# Digital_CPLD.net
KiCad netlist of a schematic drawn in Altium Designer
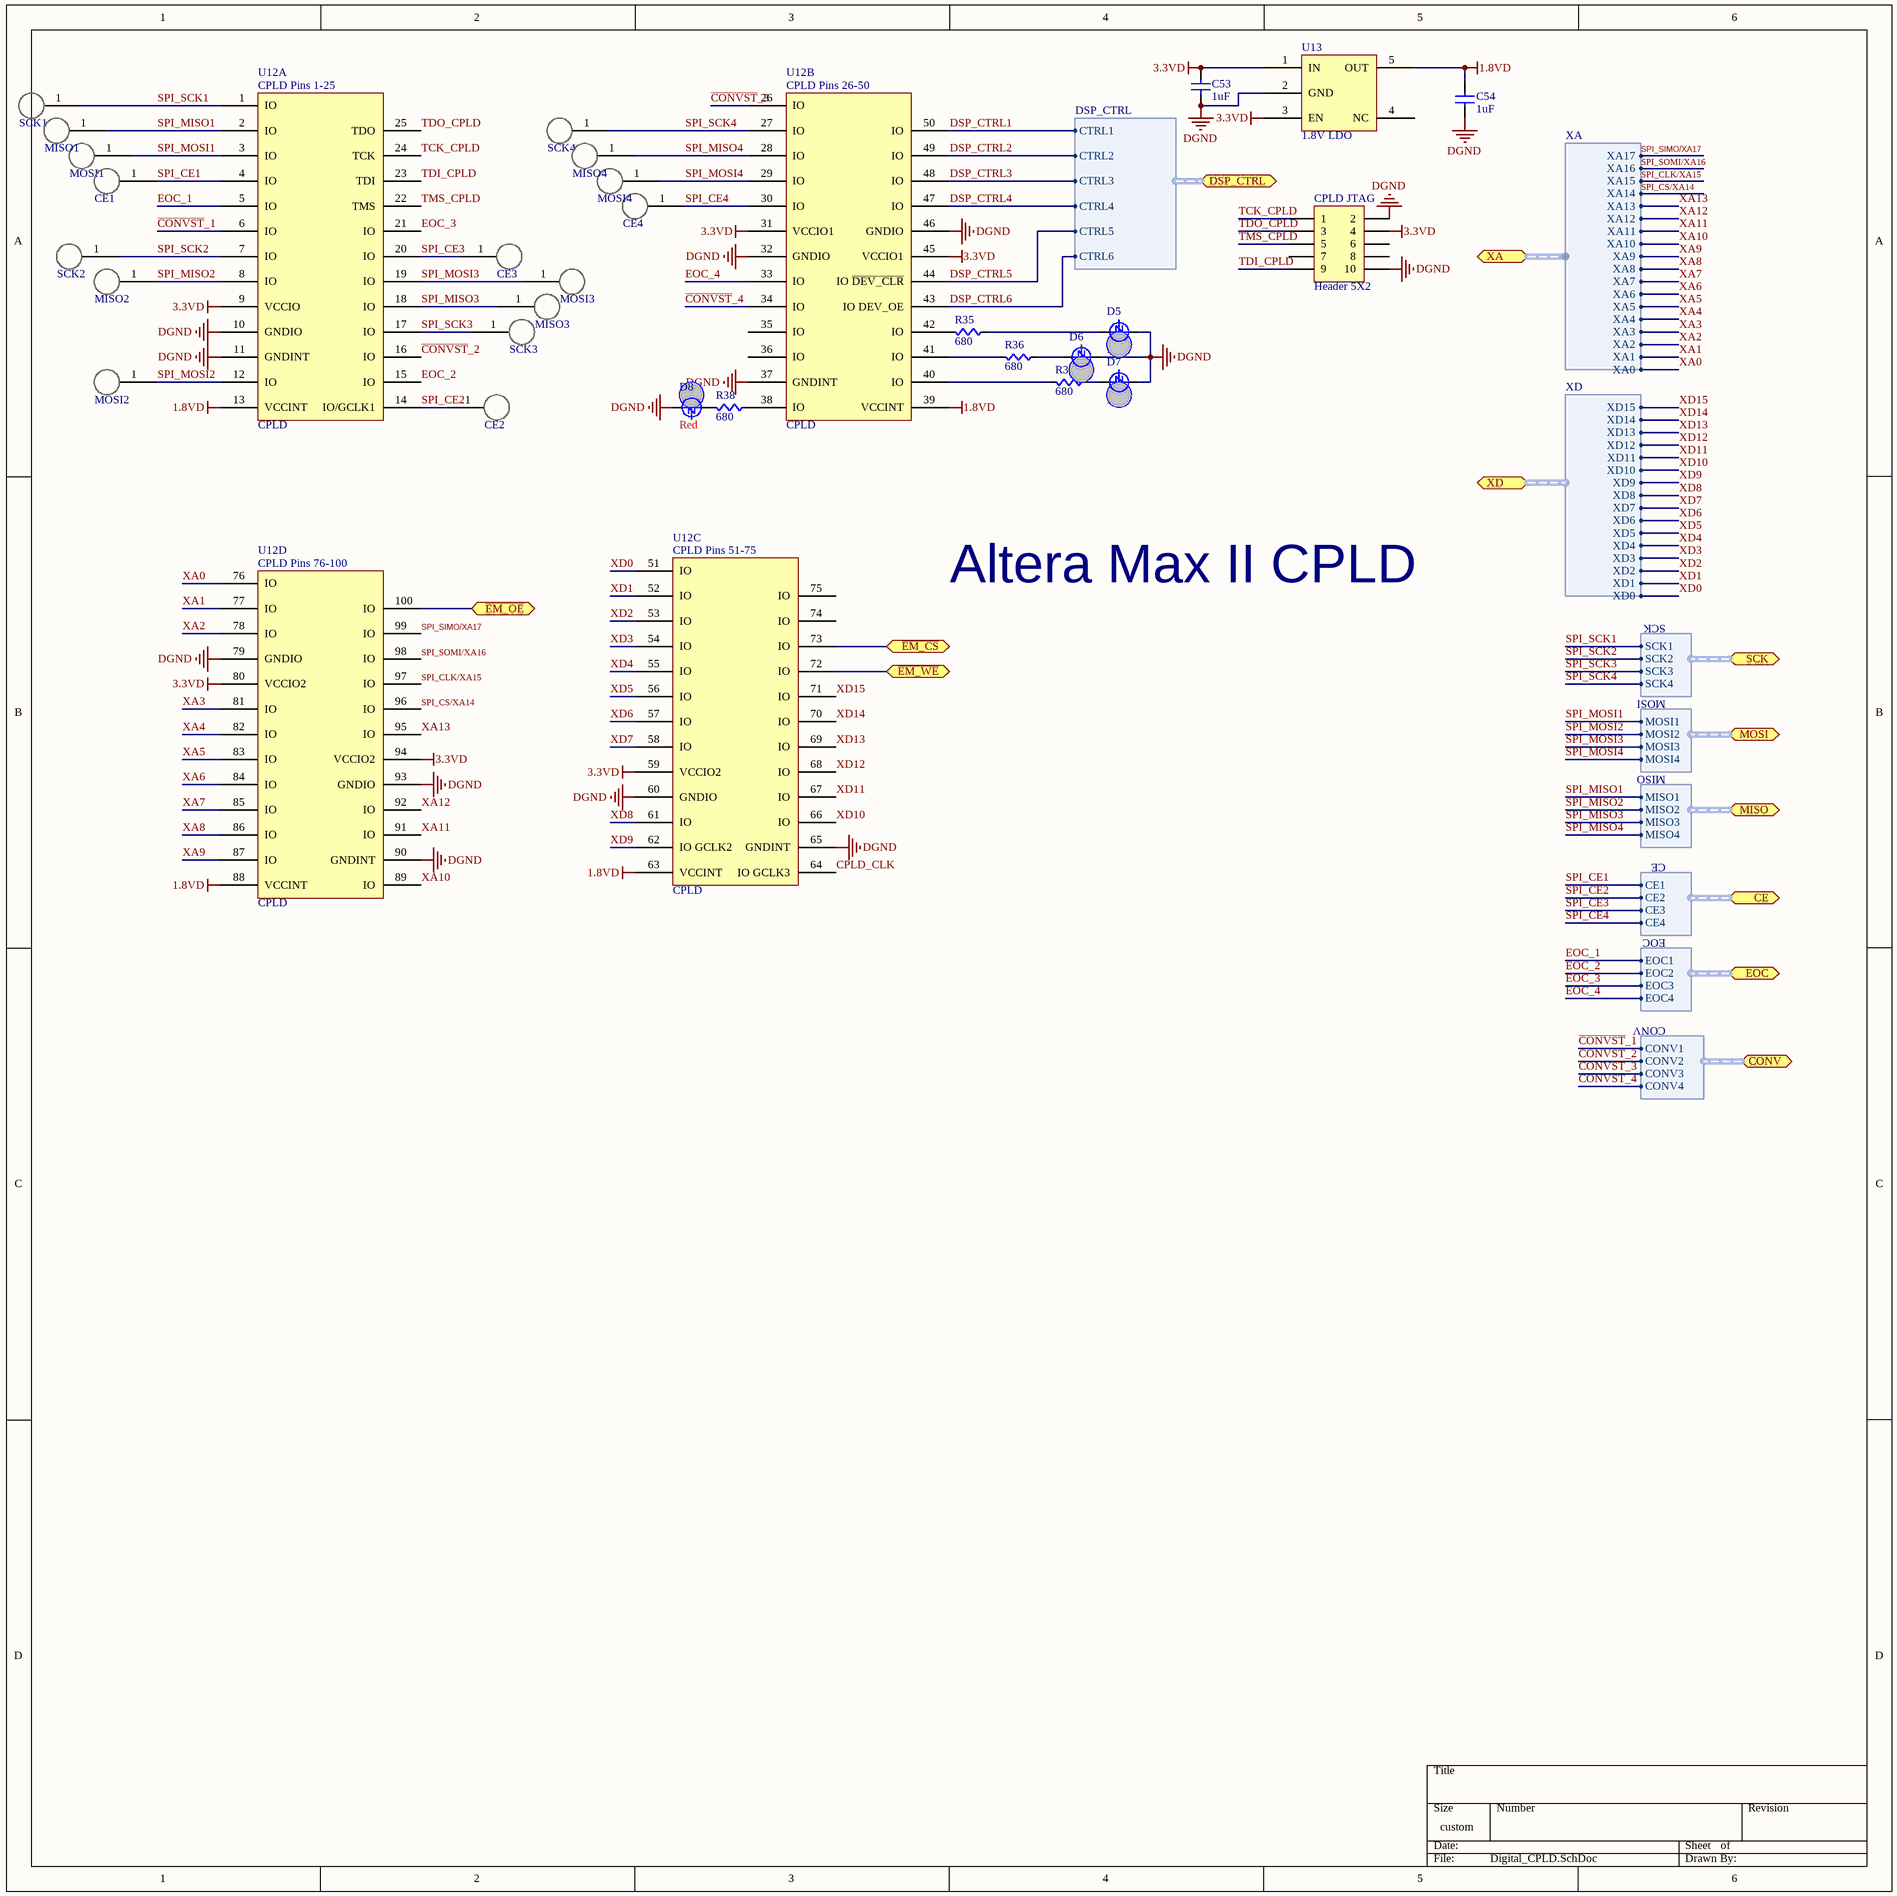
[diagram p0: Digital_CPLD.SchDoc]

(export (version "E")
  (design (tool "Eeschema 10.0.6"))
  (components
    (comp (ref "C53")
      (value "1uF")
      (footprint "CAPC0603")
      (fields (field (name "Comment") "Cap"))
      (libsource (lib "SubjuGator8") (part "Cap"))
    )
    (comp (ref "C54")
      (value "1uF")
      (footprint "CAPC0603")
      (fields (field (name "Comment") "Cap"))
      (libsource (lib "SubjuGator8") (part "Cap"))
    )
    (comp (ref "CE1")
      (value "Test_Point")
      (footprint "TP")
      (description "TEST POINT PC COMPACT .063\"D")
      (libsource (lib "Hydrophone") (part "Test_Point"))
    )
    (comp (ref "CE2")
      (value "Test_Point")
      (footprint "TP")
      (description "TEST POINT PC COMPACT .063\"D")
      (libsource (lib "Hydrophone") (part "Test_Point"))
    )
    (comp (ref "CE3")
      (value "Test_Point")
      (footprint "TP")
      (description "TEST POINT PC COMPACT .063\"D")
      (libsource (lib "Hydrophone") (part "Test_Point"))
    )
    (comp (ref "CE4")
      (value "Test_Point")
      (footprint "TP")
      (description "TEST POINT PC COMPACT .063\"D")
      (libsource (lib "Hydrophone") (part "Test_Point"))
    )
    (comp (ref "CPLD JTAG")
      (value "Header 5X2")
      (footprint "HDR2X5")
      (description "Header, 5-Pin, Dual row")
      (fields (field (name "PUBLISHER") "Altium Limited"))
      (libsource (lib "Miscellaneous Connectors") (part "Header 5X2"))
    )
    (comp (ref "D5")
      (value "LED")
      (footprint "LED0603")
      (fields (field (name "COLOR") "Red"))
      (libsource (lib "SubjuGator8") (part "LED"))
    )
    (comp (ref "D6")
      (value "LED")
      (footprint "LED0603")
      (fields (field (name "COLOR") "Red"))
      (libsource (lib "SubjuGator8") (part "LED"))
    )
    (comp (ref "D7")
      (value "LED")
      (footprint "LED0603")
      (fields (field (name "COLOR") "Red"))
      (libsource (lib "SubjuGator8") (part "LED"))
    )
    (comp (ref "D8")
      (value "LED")
      (footprint "LED0603")
      (fields (field (name "COLOR") "Red"))
      (libsource (lib "") (part "LED_1"))
    )
    (comp (ref "MISO1")
      (value "Test_Point")
      (footprint "TP")
      (description "TEST POINT PC COMPACT .063\"D")
      (libsource (lib "Hydrophone") (part "Test_Point"))
    )
    (comp (ref "MISO2")
      (value "Test_Point")
      (footprint "TP")
      (description "TEST POINT PC COMPACT .063\"D")
      (libsource (lib "Hydrophone") (part "Test_Point"))
    )
    (comp (ref "MISO3")
      (value "Test_Point")
      (footprint "TP")
      (description "TEST POINT PC COMPACT .063\"D")
      (libsource (lib "Hydrophone") (part "Test_Point"))
    )
    (comp (ref "MISO4")
      (value "Test_Point")
      (footprint "TP")
      (description "TEST POINT PC COMPACT .063\"D")
      (libsource (lib "Hydrophone") (part "Test_Point"))
    )
    (comp (ref "MOSI1")
      (value "Test_Point")
      (footprint "TP")
      (description "TEST POINT PC COMPACT .063\"D")
      (libsource (lib "Hydrophone") (part "Test_Point"))
    )
    (comp (ref "MOSI2")
      (value "Test_Point")
      (footprint "TP")
      (description "TEST POINT PC COMPACT .063\"D")
      (libsource (lib "Hydrophone") (part "Test_Point"))
    )
    (comp (ref "MOSI3")
      (value "Test_Point")
      (footprint "TP")
      (description "TEST POINT PC COMPACT .063\"D")
      (libsource (lib "Hydrophone") (part "Test_Point"))
    )
    (comp (ref "MOSI4")
      (value "Test_Point")
      (footprint "TP")
      (description "TEST POINT PC COMPACT .063\"D")
      (libsource (lib "Hydrophone") (part "Test_Point"))
    )
    (comp (ref "R35")
      (value "680")
      (footprint "RES0603")
      (fields (field (name "Comment") "Res"))
      (libsource (lib "SubjuGator8") (part "Res"))
    )
    (comp (ref "R36")
      (value "680")
      (footprint "RES0603")
      (fields (field (name "Comment") "Res"))
      (libsource (lib "SubjuGator8") (part "Res"))
    )
    (comp (ref "R37")
      (value "680")
      (footprint "RES0603")
      (fields (field (name "Comment") "Res"))
      (libsource (lib "SubjuGator8") (part "Res"))
    )
    (comp (ref "R38")
      (value "680")
      (footprint "RES0603")
      (fields (field (name "Comment") "Res"))
      (libsource (lib "SubjuGator8") (part "Res"))
    )
    (comp (ref "SCK1")
      (value "Test_Point")
      (footprint "TP")
      (description "TEST POINT PC COMPACT .063\"D")
      (libsource (lib "Hydrophone") (part "Test_Point"))
    )
    (comp (ref "SCK2")
      (value "Test_Point")
      (footprint "TP")
      (description "TEST POINT PC COMPACT .063\"D")
      (libsource (lib "Hydrophone") (part "Test_Point"))
    )
    (comp (ref "SCK3")
      (value "Test_Point")
      (footprint "TP")
      (description "TEST POINT PC COMPACT .063\"D")
      (libsource (lib "Hydrophone") (part "Test_Point"))
    )
    (comp (ref "SCK4")
      (value "Test_Point")
      (footprint "TP")
      (description "TEST POINT PC COMPACT .063\"D")
      (libsource (lib "Hydrophone") (part "Test_Point"))
    )
    (comp (ref "U12")
      (value "CPLD")
      (footprint "TQFP-100")
      (description "IC CPLD 192MC 4.7NS 100TQFP")
      (libsource (lib "SubjuGator8") (part "EPM240GT100I5N"))
    )
    (comp (ref "U13")
      (value "1.8V LDO")
      (footprint "SOT23-5n")
      (description "IC REG LDO 1.8V 0.25A SOT23-5")
      (libsource (lib "SubjuGator8") (part "LP5907"))
    )
  )
  (nets
    (net (code "10") (name "/CPLD_CLK") (class "Default")
      (node (ref "U12") (pin "64") (pinfunction "IO_GCLK3_64") (pintype "passive"))
    )
    (net (code "11") (name "/DSP_CTRL1") (class "Default")
      (node (ref "U12") (pin "50") (pinfunction "IO_50") (pintype "passive"))
    )
    (net (code "12") (name "/DSP_CTRL2") (class "Default")
      (node (ref "U12") (pin "49") (pinfunction "IO_49") (pintype "passive"))
    )
    (net (code "13") (name "/DSP_CTRL3") (class "Default")
      (node (ref "U12") (pin "48") (pinfunction "IO_48") (pintype "passive"))
    )
    (net (code "14") (name "/DSP_CTRL4") (class "Default")
      (node (ref "U12") (pin "47") (pinfunction "IO_47") (pintype "passive"))
    )
    (net (code "15") (name "/DSP_CTRL5") (class "Default")
      (node (ref "U12") (pin "44") (pinfunction "IO_~{DEV_CLR}_44") (pintype "passive"))
    )
    (net (code "16") (name "/DSP_CTRL6") (class "Default")
      (node (ref "U12") (pin "43") (pinfunction "IO_DEV_OE_43") (pintype "passive"))
    )
    (net (code "17") (name "/EOC_1") (class "Default")
      (node (ref "U12") (pin "5") (pinfunction "IO_5") (pintype "passive"))
    )
    (net (code "18") (name "/EOC_2") (class "Default")
      (node (ref "U12") (pin "15") (pinfunction "IO_15") (pintype "passive"))
    )
    (net (code "19") (name "/EOC_3") (class "Default")
      (node (ref "U12") (pin "21") (pinfunction "IO_21") (pintype "passive"))
    )
    (net (code "20") (name "/EOC_4") (class "Default")
      (node (ref "U12") (pin "33") (pinfunction "IO_33") (pintype "passive"))
    )
    (net (code "21") (name "/SPI_CE1") (class "Default")
      (node (ref "CE1") (pin "1") (pintype "passive"))
      (node (ref "U12") (pin "4") (pinfunction "IO_4") (pintype "passive"))
    )
    (net (code "22") (name "/SPI_CE2") (class "Default")
      (node (ref "CE2") (pin "1") (pintype "passive"))
      (node (ref "U12") (pin "14") (pinfunction "IO/GCLK1_14") (pintype "passive"))
    )
    (net (code "23") (name "/SPI_CE3") (class "Default")
      (node (ref "CE3") (pin "1") (pintype "passive"))
      (node (ref "U12") (pin "20") (pinfunction "IO_20") (pintype "passive"))
    )
    (net (code "24") (name "/SPI_CE4") (class "Default")
      (node (ref "CE4") (pin "1") (pintype "passive"))
      (node (ref "U12") (pin "30") (pinfunction "IO_30") (pintype "passive"))
    )
    (net (code "25") (name "/SPI_CLK{slash}XA15") (class "Default")
      (node (ref "U12") (pin "97") (pinfunction "IO_97") (pintype "passive"))
    )
    (net (code "26") (name "/SPI_CS{slash}XA14") (class "Default")
      (node (ref "U12") (pin "96") (pinfunction "IO_96") (pintype "passive"))
    )
    (net (code "27") (name "/SPI_MISO1") (class "Default")
      (node (ref "MISO1") (pin "1") (pintype "passive"))
      (node (ref "U12") (pin "2") (pinfunction "IO_2") (pintype "passive"))
    )
    (net (code "28") (name "/SPI_MISO2") (class "Default")
      (node (ref "MISO2") (pin "1") (pintype "passive"))
      (node (ref "U12") (pin "8") (pinfunction "IO_8") (pintype "passive"))
    )
    (net (code "29") (name "/SPI_MISO3") (class "Default")
      (node (ref "MISO3") (pin "1") (pintype "passive"))
      (node (ref "U12") (pin "18") (pinfunction "IO_18") (pintype "passive"))
    )
    (net (code "30") (name "/SPI_MISO4") (class "Default")
      (node (ref "MISO4") (pin "1") (pintype "passive"))
      (node (ref "U12") (pin "28") (pinfunction "IO_28") (pintype "passive"))
    )
    (net (code "31") (name "/SPI_MOSI1") (class "Default")
      (node (ref "MOSI1") (pin "1") (pintype "passive"))
      (node (ref "U12") (pin "3") (pinfunction "IO_3") (pintype "passive"))
    )
    (net (code "32") (name "/SPI_MOSI2") (class "Default")
      (node (ref "MOSI2") (pin "1") (pintype "passive"))
      (node (ref "U12") (pin "12") (pinfunction "IO_12") (pintype "passive"))
    )
    (net (code "33") (name "/SPI_MOSI3") (class "Default")
      (node (ref "MOSI3") (pin "1") (pintype "passive"))
      (node (ref "U12") (pin "19") (pinfunction "IO_19") (pintype "passive"))
    )
    (net (code "34") (name "/SPI_MOSI4") (class "Default")
      (node (ref "MOSI4") (pin "1") (pintype "passive"))
      (node (ref "U12") (pin "29") (pinfunction "IO_29") (pintype "passive"))
    )
    (net (code "35") (name "/SPI_SCK1") (class "Default")
      (node (ref "SCK1") (pin "1") (pintype "passive"))
      (node (ref "U12") (pin "1") (pinfunction "IO_1") (pintype "passive"))
    )
    (net (code "36") (name "/SPI_SCK2") (class "Default")
      (node (ref "SCK2") (pin "1") (pintype "passive"))
      (node (ref "U12") (pin "7") (pinfunction "IO_7") (pintype "passive"))
    )
    (net (code "37") (name "/SPI_SCK3") (class "Default")
      (node (ref "SCK3") (pin "1") (pintype "passive"))
      (node (ref "U12") (pin "17") (pinfunction "IO_17") (pintype "passive"))
    )
    (net (code "38") (name "/SPI_SCK4") (class "Default")
      (node (ref "SCK4") (pin "1") (pintype "passive"))
      (node (ref "U12") (pin "27") (pinfunction "IO_27") (pintype "passive"))
    )
    (net (code "39") (name "/SPI_SIMO{slash}XA17") (class "Default")
      (node (ref "U12") (pin "99") (pinfunction "IO_99") (pintype "passive"))
    )
    (net (code "40") (name "/SPI_SOMI{slash}XA16") (class "Default")
      (node (ref "U12") (pin "98") (pinfunction "IO_98") (pintype "passive"))
    )
    (net (code "41") (name "/TCK_CPLD") (class "Default")
      (node (ref "CPLD JTAG") (pin "1") (pinfunction "1_1") (pintype "passive"))
      (node (ref "U12") (pin "24") (pinfunction "TCK_24") (pintype "passive"))
    )
    (net (code "42") (name "/TDI_CPLD") (class "Default")
      (node (ref "CPLD JTAG") (pin "9") (pinfunction "9_9") (pintype "passive"))
      (node (ref "U12") (pin "23") (pinfunction "TDI_23") (pintype "passive"))
    )
    (net (code "43") (name "/TDO_CPLD") (class "Default")
      (node (ref "CPLD JTAG") (pin "3") (pinfunction "3_3") (pintype "passive"))
      (node (ref "U12") (pin "25") (pinfunction "TDO_25") (pintype "passive"))
    )
    (net (code "44") (name "/TMS_CPLD") (class "Default")
      (node (ref "CPLD JTAG") (pin "5") (pinfunction "5_5") (pintype "passive"))
      (node (ref "U12") (pin "22") (pinfunction "TMS_22") (pintype "passive"))
    )
    (net (code "45") (name "/XA0") (class "Default")
      (node (ref "U12") (pin "76") (pinfunction "IO_76") (pintype "passive"))
    )
    (net (code "46") (name "/XA1") (class "Default")
      (node (ref "U12") (pin "77") (pinfunction "IO_77") (pintype "passive"))
    )
    (net (code "47") (name "/XA2") (class "Default")
      (node (ref "U12") (pin "78") (pinfunction "IO_78") (pintype "passive"))
    )
    (net (code "48") (name "/XA3") (class "Default")
      (node (ref "U12") (pin "81") (pinfunction "IO_81") (pintype "passive"))
    )
    (net (code "49") (name "/XA4") (class "Default")
      (node (ref "U12") (pin "82") (pinfunction "IO_82") (pintype "passive"))
    )
    (net (code "50") (name "/XA5") (class "Default")
      (node (ref "U12") (pin "83") (pinfunction "IO_83") (pintype "passive"))
    )
    (net (code "51") (name "/XA6") (class "Default")
      (node (ref "U12") (pin "84") (pinfunction "IO_84") (pintype "passive"))
    )
    (net (code "52") (name "/XA7") (class "Default")
      (node (ref "U12") (pin "85") (pinfunction "IO_85") (pintype "passive"))
    )
    (net (code "53") (name "/XA8") (class "Default")
      (node (ref "U12") (pin "86") (pinfunction "IO_86") (pintype "passive"))
    )
    (net (code "54") (name "/XA9") (class "Default")
      (node (ref "U12") (pin "87") (pinfunction "IO_87") (pintype "passive"))
    )
    (net (code "55") (name "/XA10") (class "Default")
      (node (ref "U12") (pin "89") (pinfunction "IO_89") (pintype "passive"))
    )
    (net (code "56") (name "/XA11") (class "Default")
      (node (ref "U12") (pin "91") (pinfunction "IO_91") (pintype "passive"))
    )
    (net (code "57") (name "/XA12") (class "Default")
      (node (ref "U12") (pin "92") (pinfunction "IO_92") (pintype "passive"))
    )
    (net (code "58") (name "/XA13") (class "Default")
      (node (ref "U12") (pin "95") (pinfunction "IO_95") (pintype "passive"))
    )
    (net (code "59") (name "/XD0") (class "Default")
      (node (ref "U12") (pin "51") (pinfunction "IO_51") (pintype "passive"))
    )
    (net (code "60") (name "/XD1") (class "Default")
      (node (ref "U12") (pin "52") (pinfunction "IO_52") (pintype "passive"))
    )
    (net (code "61") (name "/XD2") (class "Default")
      (node (ref "U12") (pin "53") (pinfunction "IO_53") (pintype "passive"))
    )
    (net (code "62") (name "/XD3") (class "Default")
      (node (ref "U12") (pin "54") (pinfunction "IO_54") (pintype "passive"))
    )
    (net (code "63") (name "/XD4") (class "Default")
      (node (ref "U12") (pin "55") (pinfunction "IO_55") (pintype "passive"))
    )
    (net (code "64") (name "/XD5") (class "Default")
      (node (ref "U12") (pin "56") (pinfunction "IO_56") (pintype "passive"))
    )
    (net (code "65") (name "/XD6") (class "Default")
      (node (ref "U12") (pin "57") (pinfunction "IO_57") (pintype "passive"))
    )
    (net (code "66") (name "/XD7") (class "Default")
      (node (ref "U12") (pin "58") (pinfunction "IO_58") (pintype "passive"))
    )
    (net (code "67") (name "/XD8") (class "Default")
      (node (ref "U12") (pin "61") (pinfunction "IO_61") (pintype "passive"))
    )
    (net (code "68") (name "/XD9") (class "Default")
      (node (ref "U12") (pin "62") (pinfunction "IO_GCLK2_62") (pintype "passive"))
    )
    (net (code "69") (name "/XD10") (class "Default")
      (node (ref "U12") (pin "66") (pinfunction "IO_66") (pintype "passive"))
    )
    (net (code "70") (name "/XD11") (class "Default")
      (node (ref "U12") (pin "67") (pinfunction "IO_67") (pintype "passive"))
    )
    (net (code "71") (name "/XD12") (class "Default")
      (node (ref "U12") (pin "68") (pinfunction "IO_68") (pintype "passive"))
    )
    (net (code "72") (name "/XD13") (class "Default")
      (node (ref "U12") (pin "69") (pinfunction "IO_69") (pintype "passive"))
    )
    (net (code "73") (name "/XD14") (class "Default")
      (node (ref "U12") (pin "70") (pinfunction "IO_70") (pintype "passive"))
    )
    (net (code "74") (name "/XD15") (class "Default")
      (node (ref "U12") (pin "71") (pinfunction "IO_71") (pintype "passive"))
    )
    (net (code "84") (name "/~{CONVST}_1") (class "Default")
      (node (ref "U12") (pin "6") (pinfunction "IO_6") (pintype "passive"))
    )
    (net (code "85") (name "/~{CONVST}_2") (class "Default")
      (node (ref "U12") (pin "16") (pinfunction "IO_16") (pintype "passive"))
    )
    (net (code "86") (name "/~{CONVST}_3") (class "Default")
      (node (ref "U12") (pin "26") (pinfunction "IO_26") (pintype "passive"))
    )
    (net (code "87") (name "/~{CONVST}_4") (class "Default")
      (node (ref "U12") (pin "34") (pinfunction "IO_34") (pintype "passive"))
    )
    (net (code "88") (name "/~{EM_CS}") (class "Default")
      (node (ref "U12") (pin "73") (pinfunction "IO_73") (pintype "passive"))
    )
    (net (code "89") (name "/~{EM_OE}") (class "Default")
      (node (ref "U12") (pin "100") (pinfunction "IO_100") (pintype "passive"))
    )
    (net (code "90") (name "/~{EM_WE}") (class "Default")
      (node (ref "U12") (pin "72") (pinfunction "IO_72") (pintype "passive"))
    )
    (net (code "91") (name "1.8VD") (class "Default")
      (node (ref "C54") (pin "1") (pinfunction "A_1") (pintype "passive"))
      (node (ref "U12") (pin "13") (pinfunction "VCCINT_13") (pintype "passive"))
      (node (ref "U12") (pin "39") (pinfunction "VCCINT_39") (pintype "passive"))
      (node (ref "U12") (pin "63") (pinfunction "VCCINT_63") (pintype "passive"))
      (node (ref "U12") (pin "88") (pinfunction "VCCINT_88") (pintype "passive"))
      (node (ref "U13") (pin "5") (pinfunction "OUT_5") (pintype "passive"))
    )
    (net (code "92") (name "3.3VD") (class "Default")
      (node (ref "C53") (pin "1") (pinfunction "A_1") (pintype "passive"))
      (node (ref "CPLD JTAG") (pin "4") (pinfunction "4_4") (pintype "passive"))
      (node (ref "U12") (pin "31") (pinfunction "VCCIO1_31") (pintype "passive"))
      (node (ref "U12") (pin "45") (pinfunction "VCCIO1_45") (pintype "passive"))
      (node (ref "U12") (pin "59") (pinfunction "VCCIO2_59") (pintype "passive"))
      (node (ref "U12") (pin "80") (pinfunction "VCCIO2_80") (pintype "passive"))
      (node (ref "U12") (pin "9") (pinfunction "VCCIO_9") (pintype "passive"))
      (node (ref "U12") (pin "94") (pinfunction "VCCIO2_94") (pintype "passive"))
      (node (ref "U13") (pin "1") (pinfunction "IN_1") (pintype "passive"))
      (node (ref "U13") (pin "3") (pinfunction "EN_3") (pintype "passive"))
    )
    (net (code "93") (name "DGND") (class "Default")
      (node (ref "C53") (pin "2") (pinfunction "B_2") (pintype "passive"))
      (node (ref "C54") (pin "2") (pinfunction "B_2") (pintype "passive"))
      (node (ref "CPLD JTAG") (pin "10") (pinfunction "10_10") (pintype "passive"))
      (node (ref "CPLD JTAG") (pin "2") (pinfunction "2_2") (pintype "passive"))
      (node (ref "D5") (pin "C") (pinfunction "C_C") (pintype "passive"))
      (node (ref "D6") (pin "C") (pinfunction "C_C") (pintype "passive"))
      (node (ref "D7") (pin "C") (pinfunction "C_C") (pintype "passive"))
      (node (ref "D8") (pin "C") (pinfunction "C_C") (pintype "passive"))
      (node (ref "U12") (pin "10") (pinfunction "GNDIO_10") (pintype "passive"))
      (node (ref "U12") (pin "11") (pinfunction "GNDINT_11") (pintype "passive"))
      (node (ref "U12") (pin "32") (pinfunction "GNDIO_32") (pintype "passive"))
      (node (ref "U12") (pin "37") (pinfunction "GNDINT_37") (pintype "passive"))
      (node (ref "U12") (pin "46") (pinfunction "GNDIO_46") (pintype "passive"))
      (node (ref "U12") (pin "60") (pinfunction "GNDIO_60") (pintype "passive"))
      (node (ref "U12") (pin "65") (pinfunction "GNDINT_65") (pintype "passive"))
      (node (ref "U12") (pin "79") (pinfunction "GNDIO_79") (pintype "passive"))
      (node (ref "U12") (pin "90") (pinfunction "GNDINT_90") (pintype "passive"))
      (node (ref "U12") (pin "93") (pinfunction "GNDIO_93") (pintype "passive"))
      (node (ref "U13") (pin "2") (pinfunction "GND_2") (pintype "passive"))
    )
    (net (code "94") (name "Net-(R35-A)") (class "Default")
      (node (ref "R35") (pin "1") (pinfunction "A_1") (pintype "passive"))
      (node (ref "U12") (pin "42") (pinfunction "IO_42") (pintype "passive"))
    )
    (net (code "95") (name "Net-(R35-B)") (class "Default")
      (node (ref "D5") (pin "A") (pinfunction "A_A") (pintype "passive"))
      (node (ref "R35") (pin "2") (pinfunction "B_2") (pintype "passive"))
    )
    (net (code "96") (name "Net-(R36-A)") (class "Default")
      (node (ref "R36") (pin "1") (pinfunction "A_1") (pintype "passive"))
      (node (ref "U12") (pin "41") (pinfunction "IO_41") (pintype "passive"))
    )
    (net (code "97") (name "Net-(R36-B)") (class "Default")
      (node (ref "D6") (pin "A") (pinfunction "A_A") (pintype "passive"))
      (node (ref "R36") (pin "2") (pinfunction "B_2") (pintype "passive"))
    )
    (net (code "98") (name "Net-(R37-A)") (class "Default")
      (node (ref "R37") (pin "1") (pinfunction "A_1") (pintype "passive"))
      (node (ref "U12") (pin "40") (pinfunction "IO_40") (pintype "passive"))
    )
    (net (code "99") (name "Net-(R37-B)") (class "Default")
      (node (ref "D7") (pin "A") (pinfunction "A_A") (pintype "passive"))
      (node (ref "R37") (pin "2") (pinfunction "B_2") (pintype "passive"))
    )
    (net (code "100") (name "Net-(R38-A)") (class "Default")
      (node (ref "D8") (pin "A") (pinfunction "A_A") (pintype "passive"))
      (node (ref "R38") (pin "1") (pinfunction "A_1") (pintype "passive"))
    )
    (net (code "101") (name "Net-(R38-B)") (class "Default")
      (node (ref "R38") (pin "2") (pinfunction "B_2") (pintype "passive"))
      (node (ref "U12") (pin "38") (pinfunction "IO_38") (pintype "passive"))
    )
    (net (code "102") (name "unconnected-(CPLD JTAG-Pad6)") (class "Default")
      (node (ref "CPLD JTAG") (pin "6") (pinfunction "6_6") (pintype "passive"))
    )
    (net (code "103") (name "unconnected-(CPLD JTAG-Pad7)") (class "Default")
      (node (ref "CPLD JTAG") (pin "7") (pinfunction "7_7") (pintype "passive"))
    )
    (net (code "104") (name "unconnected-(CPLD JTAG-Pad8)") (class "Default")
      (node (ref "CPLD JTAG") (pin "8") (pinfunction "8_8") (pintype "passive"))
    )
    (net (code "105") (name "unconnected-(U12B-IO-Pad35)") (class "Default")
      (node (ref "U12") (pin "35") (pinfunction "IO_35") (pintype "passive"))
    )
    (net (code "106") (name "unconnected-(U12B-IO-Pad36)") (class "Default")
      (node (ref "U12") (pin "36") (pinfunction "IO_36") (pintype "passive"))
    )
    (net (code "107") (name "unconnected-(U12C-IO-Pad74)") (class "Default")
      (node (ref "U12") (pin "74") (pinfunction "IO_74") (pintype "passive"))
    )
    (net (code "108") (name "unconnected-(U12C-IO-Pad75)") (class "Default")
      (node (ref "U12") (pin "75") (pinfunction "IO_75") (pintype "passive"))
    )
    (net (code "109") (name "unconnected-(U13-NC-Pad4)") (class "Default")
      (node (ref "U13") (pin "4") (pinfunction "NC_4") (pintype "passive"))
    )
  )
)
